# NZN_Breakout.net
KiCad netlist of a schematic drawn in EAGLE
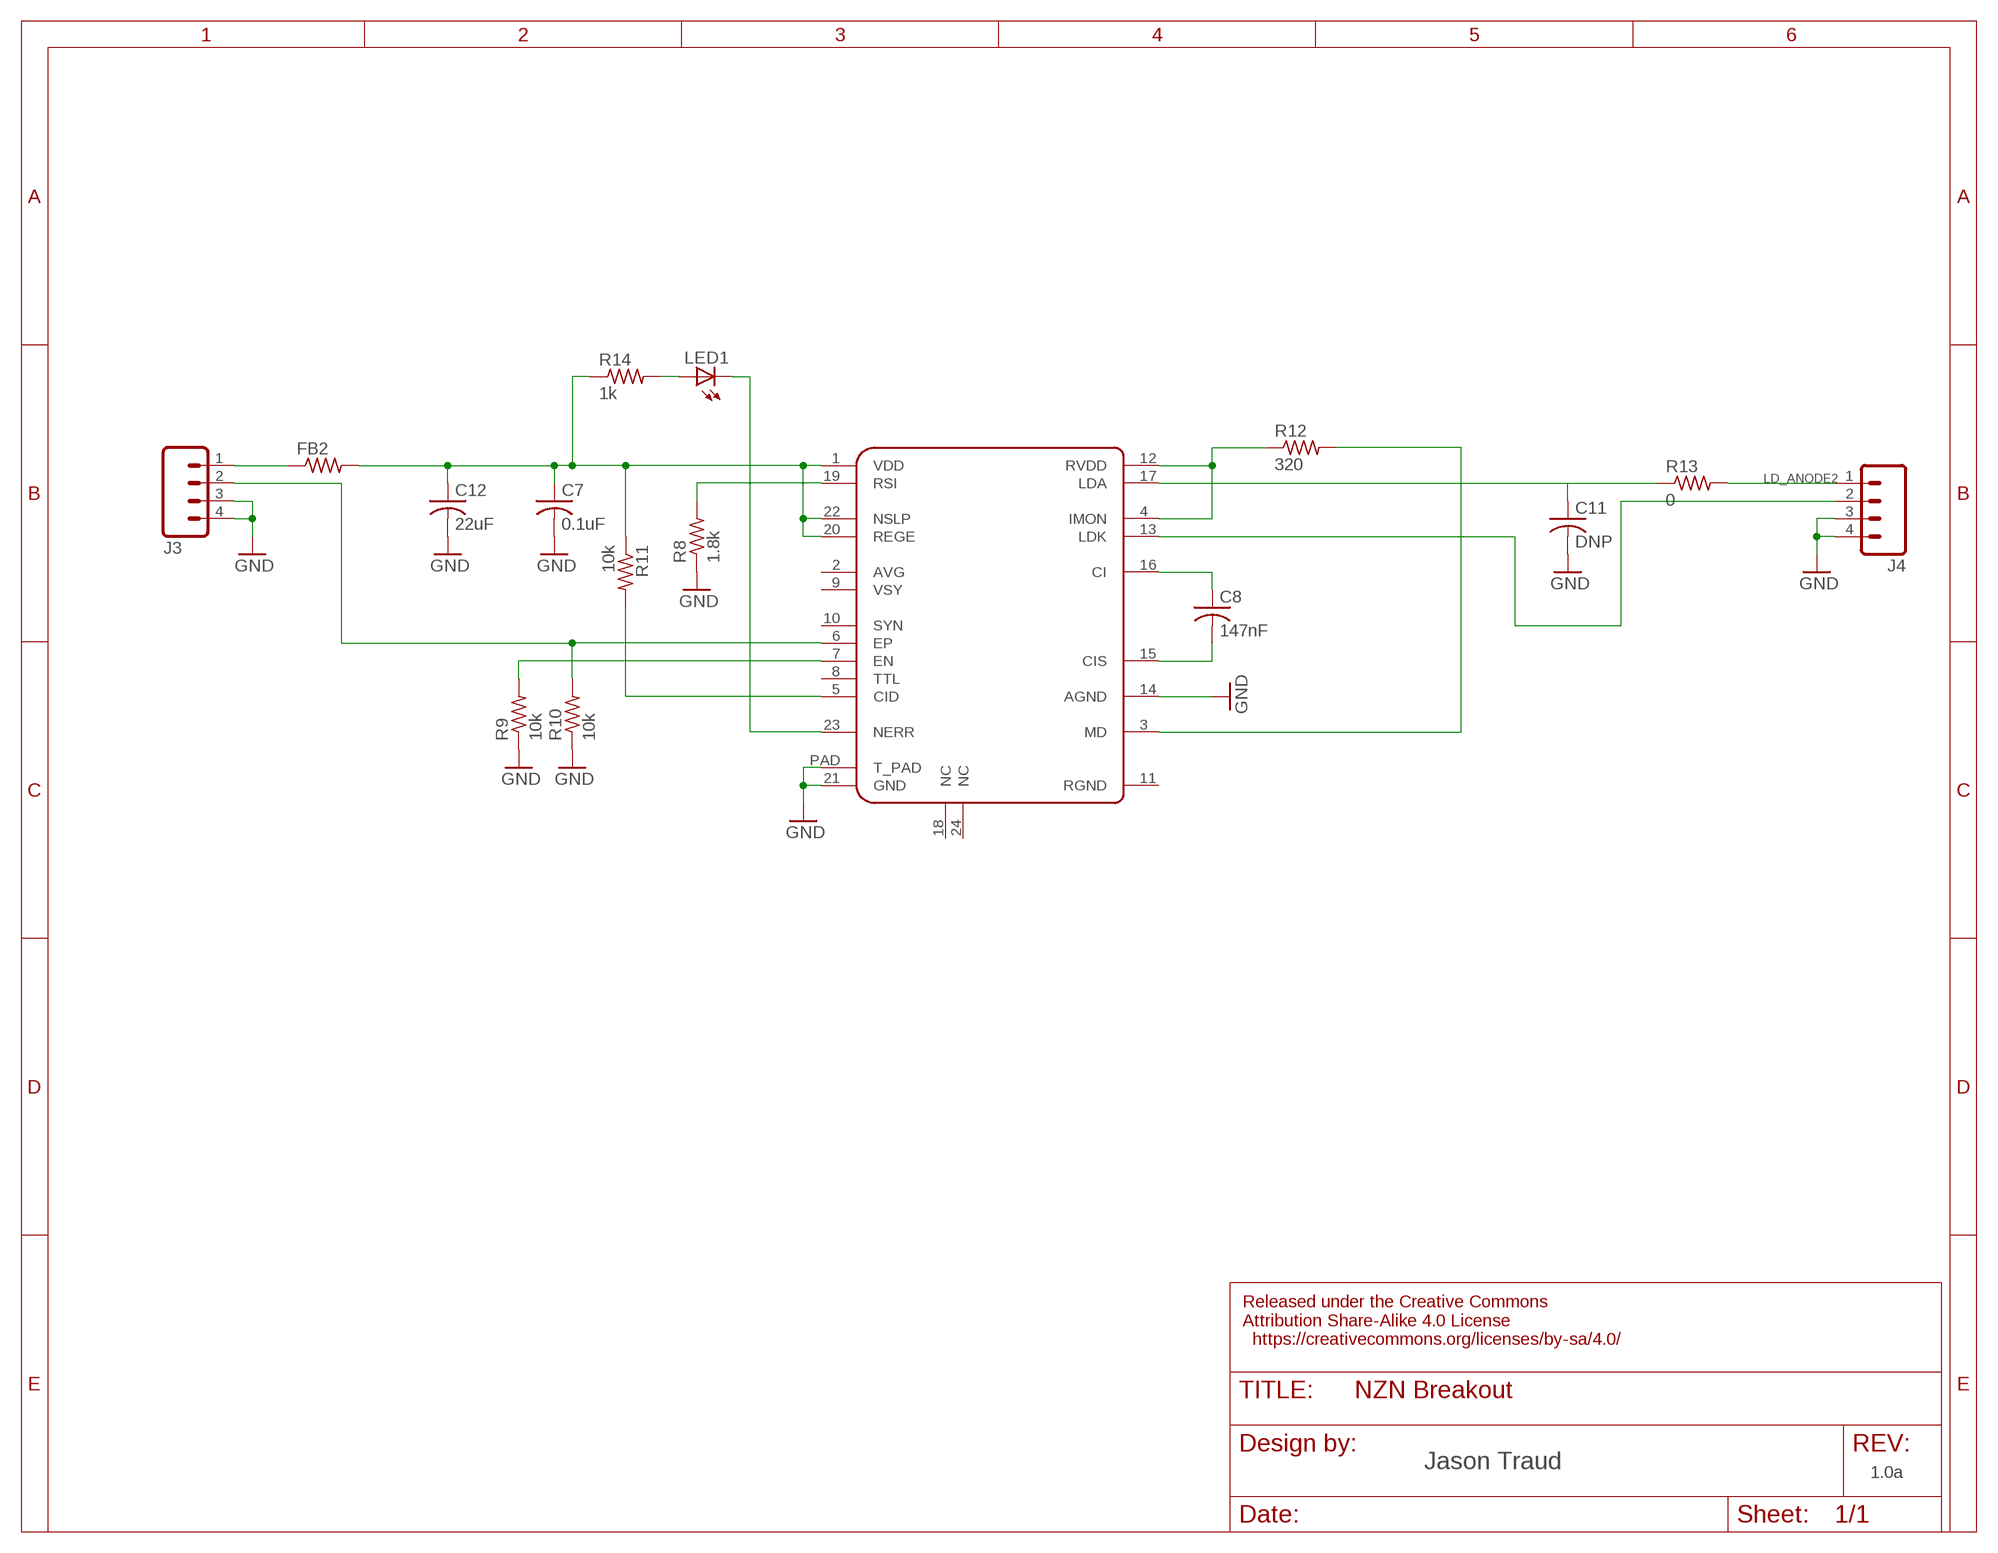
[diagram p0: schematic, sheet 1]

(export (version "E")
  (design (tool "Eeschema 10.0.6"))
  (components
    (comp (ref "C7")
      (value "0.1uF")
      (footprint "eagle-import:C0402")
      (libsource (lib "eagle-import") (part "C-USC0402"))
    )
    (comp (ref "C8")
      (value "147nF")
      (footprint "eagle-import:C0402")
      (libsource (lib "eagle-import") (part "C-USC0402"))
    )
    (comp (ref "C11")
      (value "DNP")
      (footprint "eagle-import:C0805")
      (libsource (lib "eagle-import") (part "C-USC0805"))
    )
    (comp (ref "C12")
      (value "22uF")
      (footprint "eagle-import:C1206")
      (libsource (lib "eagle-import") (part "C-USC1206"))
    )
    (comp (ref "FB2")
      (value "R-US_R0805")
      (footprint "eagle-import:R0805")
      (libsource (lib "eagle-import") (part "R-US_R0805"))
    )
    (comp (ref "J3")
      (value "2X2")
      (footprint "eagle-import:2X2_1.27MM")
      (libsource (lib "eagle-import") (part "2X2"))
    )
    (comp (ref "J4")
      (value "2X2")
      (footprint "eagle-import:2X2_1.27MM")
      (libsource (lib "eagle-import") (part "2X2"))
    )
    (comp (ref "LED1")
      (value "LEDSML0805")
      (footprint "eagle-import:SML0805")
      (libsource (lib "eagle-import") (part "LEDSML0805"))
    )
    (comp (ref "R8")
      (value "1.8k")
      (footprint "eagle-import:R0402")
      (libsource (lib "eagle-import") (part "R-US_R0402"))
    )
    (comp (ref "R9")
      (value "10k")
      (footprint "eagle-import:R0402")
      (libsource (lib "eagle-import") (part "R-US_R0402"))
    )
    (comp (ref "R10")
      (value "10k")
      (footprint "eagle-import:R0402")
      (libsource (lib "eagle-import") (part "R-US_R0402"))
    )
    (comp (ref "R11")
      (value "10k")
      (footprint "eagle-import:R0402")
      (libsource (lib "eagle-import") (part "R-US_R0402"))
    )
    (comp (ref "R12")
      (value "320")
      (footprint "eagle-import:R0402")
      (libsource (lib "eagle-import") (part "R-US_R0402"))
    )
    (comp (ref "R13")
      (value "0")
      (footprint "eagle-import:R0805")
      (libsource (lib "eagle-import") (part "R-US_R0805"))
    )
    (comp (ref "R14")
      (value "1k")
      (footprint "eagle-import:R0402")
      (libsource (lib "eagle-import") (part "R-US_R0402"))
    )
    (comp (ref "U$1")
      (value "IC-NZN")
      (footprint "eagle-import:QFN24_PAD")
      (libsource (lib "eagle-import") (part "IC-NZN"))
    )
  )
  (nets
    (net (code "1") (name "/LD_ANODE2") (class "Default")
      (node (ref "J4") (pin "1") (pinfunction "1_1") (pintype "passive"))
      (node (ref "R13") (pin "2") (pinfunction "2_2") (pintype "passive"))
    )
    (net (code "2") (name "GND") (class "Default")
      (node (ref "C11") (pin "2") (pinfunction "2_2") (pintype "passive"))
      (node (ref "C12") (pin "2") (pinfunction "2_2") (pintype "passive"))
      (node (ref "C7") (pin "2") (pinfunction "2_2") (pintype "passive"))
      (node (ref "J3") (pin "3") (pinfunction "3_3") (pintype "passive"))
      (node (ref "J3") (pin "4") (pinfunction "4_4") (pintype "passive"))
      (node (ref "J4") (pin "3") (pinfunction "3_3") (pintype "passive"))
      (node (ref "J4") (pin "4") (pinfunction "4_4") (pintype "passive"))
      (node (ref "R10") (pin "1") (pinfunction "1_1") (pintype "passive"))
      (node (ref "R8") (pin "1") (pinfunction "1_1") (pintype "passive"))
      (node (ref "R9") (pin "1") (pinfunction "1_1") (pintype "passive"))
      (node (ref "U$1") (pin "14") (pinfunction "AGND_14") (pintype "bidirectional"))
      (node (ref "U$1") (pin "21") (pinfunction "GND_21") (pintype "bidirectional"))
      (node (ref "U$1") (pin "PAD") (pinfunction "T_PAD_PAD") (pintype "bidirectional"))
    )
    (net (code "3") (name "Net-(FB2-Pad1)") (class "Default")
      (node (ref "FB2") (pin "1") (pinfunction "1_1") (pintype "passive"))
      (node (ref "J3") (pin "1") (pinfunction "1_1") (pintype "passive"))
    )
    (net (code "4") (name "Net-(LED1-PadA)") (class "Default")
      (node (ref "LED1") (pin "A") (pinfunction "A_A") (pintype "passive"))
      (node (ref "R14") (pin "2") (pinfunction "2_2") (pintype "passive"))
    )
    (net (code "5") (name "Net-(U$1-CI)") (class "Default")
      (node (ref "C8") (pin "1") (pinfunction "1_1") (pintype "passive"))
      (node (ref "U$1") (pin "16") (pinfunction "CI_16") (pintype "bidirectional"))
    )
    (net (code "6") (name "Net-(U$1-CID)") (class "Default")
      (node (ref "R11") (pin "2") (pinfunction "2_2") (pintype "passive"))
      (node (ref "U$1") (pin "5") (pinfunction "CID_5") (pintype "bidirectional"))
    )
    (net (code "7") (name "Net-(U$1-CIS)") (class "Default")
      (node (ref "C8") (pin "2") (pinfunction "2_2") (pintype "passive"))
      (node (ref "U$1") (pin "15") (pinfunction "CIS_15") (pintype "bidirectional"))
    )
    (net (code "8") (name "Net-(U$1-EN)") (class "Default")
      (node (ref "R9") (pin "2") (pinfunction "2_2") (pintype "passive"))
      (node (ref "U$1") (pin "7") (pinfunction "EN_7") (pintype "bidirectional"))
    )
    (net (code "9") (name "Net-(U$1-EP)") (class "Default")
      (node (ref "J3") (pin "2") (pinfunction "2_2") (pintype "passive"))
      (node (ref "R10") (pin "2") (pinfunction "2_2") (pintype "passive"))
      (node (ref "U$1") (pin "6") (pinfunction "EP_6") (pintype "bidirectional"))
    )
    (net (code "10") (name "Net-(U$1-IMON)") (class "Default")
      (node (ref "R12") (pin "1") (pinfunction "1_1") (pintype "passive"))
      (node (ref "U$1") (pin "12") (pinfunction "RVDD_12") (pintype "bidirectional"))
      (node (ref "U$1") (pin "4") (pinfunction "IMON_4") (pintype "bidirectional"))
    )
    (net (code "11") (name "Net-(U$1-LDA)") (class "Default")
      (node (ref "C11") (pin "1") (pinfunction "1_1") (pintype "passive"))
      (node (ref "R13") (pin "1") (pinfunction "1_1") (pintype "passive"))
      (node (ref "U$1") (pin "17") (pinfunction "LDA_17") (pintype "bidirectional"))
    )
    (net (code "12") (name "Net-(U$1-LDK)") (class "Default")
      (node (ref "J4") (pin "2") (pinfunction "2_2") (pintype "passive"))
      (node (ref "U$1") (pin "13") (pinfunction "LDK_13") (pintype "bidirectional"))
    )
    (net (code "13") (name "Net-(U$1-MD)") (class "Default")
      (node (ref "R12") (pin "2") (pinfunction "2_2") (pintype "passive"))
      (node (ref "U$1") (pin "3") (pinfunction "MD_3") (pintype "bidirectional"))
    )
    (net (code "14") (name "Net-(U$1-NERR)") (class "Default")
      (node (ref "LED1") (pin "C") (pinfunction "C_C") (pintype "passive"))
      (node (ref "U$1") (pin "23") (pinfunction "NERR_23") (pintype "bidirectional"))
    )
    (net (code "15") (name "Net-(U$1-NSLP)") (class "Default")
      (node (ref "C12") (pin "1") (pinfunction "1_1") (pintype "passive"))
      (node (ref "C7") (pin "1") (pinfunction "1_1") (pintype "passive"))
      (node (ref "FB2") (pin "2") (pinfunction "2_2") (pintype "passive"))
      (node (ref "R11") (pin "1") (pinfunction "1_1") (pintype "passive"))
      (node (ref "R14") (pin "1") (pinfunction "1_1") (pintype "passive"))
      (node (ref "U$1") (pin "1") (pinfunction "VDD_1") (pintype "bidirectional"))
      (node (ref "U$1") (pin "20") (pinfunction "REGE_20") (pintype "bidirectional"))
      (node (ref "U$1") (pin "22") (pinfunction "NSLP_22") (pintype "bidirectional"))
    )
    (net (code "16") (name "Net-(U$1-RSI)") (class "Default")
      (node (ref "R8") (pin "2") (pinfunction "2_2") (pintype "passive"))
      (node (ref "U$1") (pin "19") (pinfunction "RSI_19") (pintype "bidirectional"))
    )
    (net (code "17") (name "unconnected-(U$1-AVG-Pad2)") (class "Default")
      (node (ref "U$1") (pin "2") (pinfunction "AVG_2") (pintype "bidirectional"))
    )
    (net (code "18") (name "unconnected-(U$1-NC-Pad18)") (class "Default")
      (node (ref "U$1") (pin "18") (pinfunction "NC_18") (pintype "bidirectional"))
    )
    (net (code "19") (name "unconnected-(U$1-NC-Pad24)") (class "Default")
      (node (ref "U$1") (pin "24") (pinfunction "NC_24") (pintype "bidirectional"))
    )
    (net (code "20") (name "unconnected-(U$1-RGND-Pad11)") (class "Default")
      (node (ref "U$1") (pin "11") (pinfunction "RGND_11") (pintype "bidirectional"))
    )
    (net (code "21") (name "unconnected-(U$1-SYN-Pad10)") (class "Default")
      (node (ref "U$1") (pin "10") (pinfunction "SYN_10") (pintype "bidirectional"))
    )
    (net (code "22") (name "unconnected-(U$1-TTL-Pad8)") (class "Default")
      (node (ref "U$1") (pin "8") (pinfunction "TTL_8") (pintype "bidirectional"))
    )
    (net (code "23") (name "unconnected-(U$1-VSY-Pad9)") (class "Default")
      (node (ref "U$1") (pin "9") (pinfunction "VSY_9") (pintype "bidirectional"))
    )
  )
)
